# power.net
KiCad netlist of a schematic drawn in Altium Designer
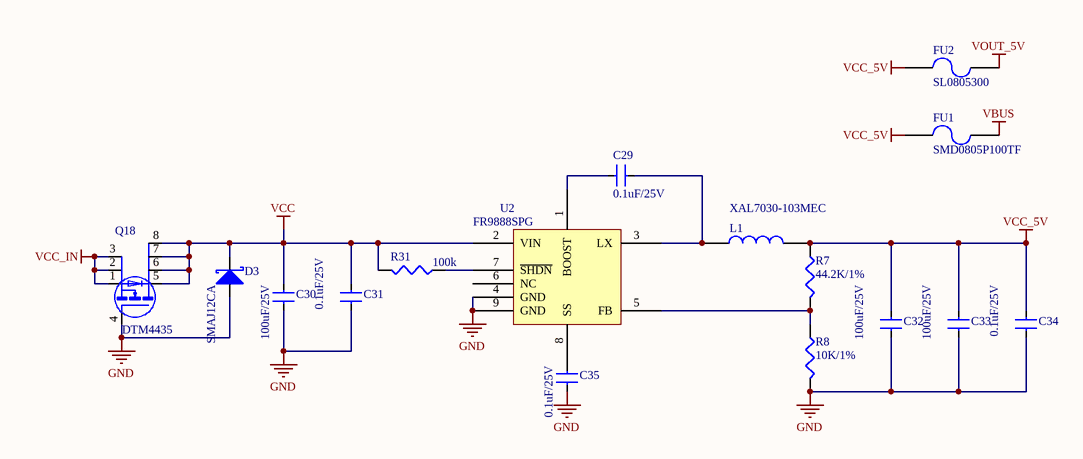
[diagram p0: power.SchDoc]

(export (version "E")
  (design (tool "Eeschema 10.0.6"))
  (components
    (comp (ref "C29")
      (value "0.1uF/25V")
      (footprint "0603C")
      (description "CCX85-103")
      (libsource (lib "无极性电容") (part "0.01UF"))
    )
    (comp (ref "C30")
      (value "100uF/25V")
      (footprint "1210C")
      (description "CCX85-103")
      (libsource (lib "无极性电容") (part "0.01UF"))
    )
    (comp (ref "C31")
      (value "0.1uF/25V")
      (footprint "0603C")
      (description "CCX85-103")
      (libsource (lib "无极性电容") (part "0.01UF"))
    )
    (comp (ref "C32")
      (value "100uF/25V")
      (footprint "1210C")
      (description "CCX85-103")
      (libsource (lib "无极性电容") (part "0.01UF"))
    )
    (comp (ref "C33")
      (value "100uF/25V")
      (footprint "1210C")
      (description "CCX85-103")
      (libsource (lib "无极性电容") (part "0.01UF"))
    )
    (comp (ref "C34")
      (value "0.1uF/25V")
      (footprint "0603C")
      (description "CCX85-103")
      (libsource (lib "无极性电容") (part "0.01UF"))
    )
    (comp (ref "C35")
      (value "0.1uF/25V")
      (footprint "0603C")
      (description "CCX85-103")
      (libsource (lib "无极性电容") (part "0.01UF"))
    )
    (comp (ref "D3")
      (value "SMAJ12CA")
      (footprint "SMA")
      (description "Schottky Diode")
      (libsource (lib "*") (part "DIODE S"))
    )
    (comp (ref "FU1")
      (value "SMD0805P100TF")
      (footprint "F0805")
      (description "Fuse")
      (libsource (lib "SM") (part "FUSE2"))
    )
    (comp (ref "FU2")
      (value "SL0805300")
      (footprint "F0805")
      (description "Fuse")
      (libsource (lib "SM") (part "FUSE2"))
    )
    (comp (ref "L1") (value "XAL7030-103MEC") (footprint "XAL7030") (libsource (lib "*") (part "INDUCTOR")))
    (comp (ref "Q18")
      (value "DTM4435")
      (footprint "SO-8")
      (description "Si4004DY")
      (libsource (lib "Schlib_20110825") (part "Si4004DY"))
    )
    (comp (ref "R7")
      (value "44.2K/1%")
      (footprint "0603R")
      (description "Resistor")
      (fields (field (name "PUBLISHER") "Altium Limited"))
      (libsource (lib "SM") (part "Res3"))
    )
    (comp (ref "R8")
      (value "10K/1%")
      (footprint "0603R")
      (description "Resistor")
      (fields (field (name "PUBLISHER") "Altium Limited"))
      (libsource (lib "SM") (part "Res3"))
    )
    (comp (ref "R31")
      (value "100k")
      (footprint "0603R")
      (description "Resistor")
      (fields (field (name "PUBLISHER") "Altium Limited"))
      (libsource (lib "SM") (part "Res3"))
    )
    (comp (ref "U2")
      (value "FR9888SPG")
      (footprint "SOP120P600-8N")
      (libsource (lib "stm32") (part "FR9888SPG"))
    )
  )
  (nets
    (net (code "1") (name "GND") (class "Default")
      (node (ref "C30") (pin "2") (pinfunction "2_2") (pintype "passive"))
      (node (ref "C31") (pin "2") (pinfunction "2_2") (pintype "passive"))
      (node (ref "C32") (pin "2") (pinfunction "2_2") (pintype "passive"))
      (node (ref "C33") (pin "2") (pinfunction "2_2") (pintype "passive"))
      (node (ref "C34") (pin "2") (pinfunction "2_2") (pintype "passive"))
      (node (ref "C35") (pin "2") (pinfunction "2_2") (pintype "passive"))
      (node (ref "D3") (pin "1") (pinfunction "A_1") (pintype "passive"))
      (node (ref "Q18") (pin "4") (pinfunction "G_4") (pintype "passive"))
      (node (ref "R8") (pin "2") (pinfunction "2_2") (pintype "passive"))
      (node (ref "U2") (pin "4") (pinfunction "GND_4") (pintype "passive"))
      (node (ref "U2") (pin "9") (pinfunction "GND_9") (pintype "passive"))
    )
    (net (code "2") (name "Net-(U2-BOOST)") (class "Default")
      (node (ref "C29") (pin "1") (pinfunction "1_1") (pintype "passive"))
      (node (ref "U2") (pin "1") (pinfunction "BOOST_1") (pintype "passive"))
    )
    (net (code "3") (name "Net-(U2-FB)") (class "Default")
      (node (ref "R7") (pin "2") (pinfunction "2_2") (pintype "passive"))
      (node (ref "R8") (pin "1") (pinfunction "1_1") (pintype "passive"))
      (node (ref "U2") (pin "5") (pinfunction "FB_5") (pintype "passive"))
    )
    (net (code "4") (name "Net-(U2-LX)") (class "Default")
      (node (ref "C29") (pin "2") (pinfunction "2_2") (pintype "passive"))
      (node (ref "L1") (pin "1") (pinfunction "1_1") (pintype "passive"))
      (node (ref "U2") (pin "3") (pinfunction "LX_3") (pintype "passive"))
    )
    (net (code "5") (name "Net-(U2-SS)") (class "Default")
      (node (ref "C35") (pin "1") (pinfunction "1_1") (pintype "passive"))
      (node (ref "U2") (pin "8") (pinfunction "SS_8") (pintype "passive"))
    )
    (net (code "6") (name "Net-(U2-~{SHDN})") (class "Default")
      (node (ref "R31") (pin "1") (pinfunction "1_1") (pintype "passive"))
      (node (ref "U2") (pin "7") (pinfunction "~{SHDN}_7") (pintype "passive"))
    )
    (net (code "7") (name "VBUS") (class "Default")
      (node (ref "FU1") (pin "2") (pinfunction "2_2") (pintype "passive"))
    )
    (net (code "8") (name "VCC") (class "Default")
      (node (ref "C30") (pin "1") (pinfunction "1_1") (pintype "passive"))
      (node (ref "C31") (pin "1") (pinfunction "1_1") (pintype "passive"))
      (node (ref "D3") (pin "2") (pinfunction "K_2") (pintype "passive"))
      (node (ref "Q18") (pin "5") (pinfunction "D_5") (pintype "passive"))
      (node (ref "Q18") (pin "6") (pinfunction "D_6") (pintype "passive"))
      (node (ref "Q18") (pin "7") (pinfunction "D_7") (pintype "passive"))
      (node (ref "Q18") (pin "8") (pinfunction "D_8") (pintype "passive"))
      (node (ref "R31") (pin "2") (pinfunction "2_2") (pintype "passive"))
      (node (ref "U2") (pin "2") (pinfunction "VIN_2") (pintype "passive"))
    )
    (net (code "9") (name "VCC_5V") (class "Default")
      (node (ref "C32") (pin "1") (pinfunction "1_1") (pintype "passive"))
      (node (ref "C33") (pin "1") (pinfunction "1_1") (pintype "passive"))
      (node (ref "C34") (pin "1") (pinfunction "1_1") (pintype "passive"))
      (node (ref "FU1") (pin "1") (pinfunction "1_1") (pintype "passive"))
      (node (ref "FU2") (pin "1") (pinfunction "1_1") (pintype "passive"))
      (node (ref "L1") (pin "2") (pinfunction "2_2") (pintype "passive"))
      (node (ref "R7") (pin "1") (pinfunction "1_1") (pintype "passive"))
    )
    (net (code "10") (name "VCC_IN") (class "Default")
      (node (ref "Q18") (pin "1") (pinfunction "S_1") (pintype "passive"))
      (node (ref "Q18") (pin "2") (pinfunction "S_2") (pintype "passive"))
      (node (ref "Q18") (pin "3") (pinfunction "S_3") (pintype "passive"))
    )
    (net (code "11") (name "VOUT_5V") (class "Default")
      (node (ref "FU2") (pin "2") (pinfunction "2_2") (pintype "passive"))
    )
    (net (code "12") (name "unconnected-(U2-NC-Pad6)") (class "Default")
      (node (ref "U2") (pin "6") (pinfunction "NC_6") (pintype "passive"))
    )
  )
)
